# Excelsior488nm_Controller_Schematic.net
KiCad netlist of a schematic drawn in EAGLE
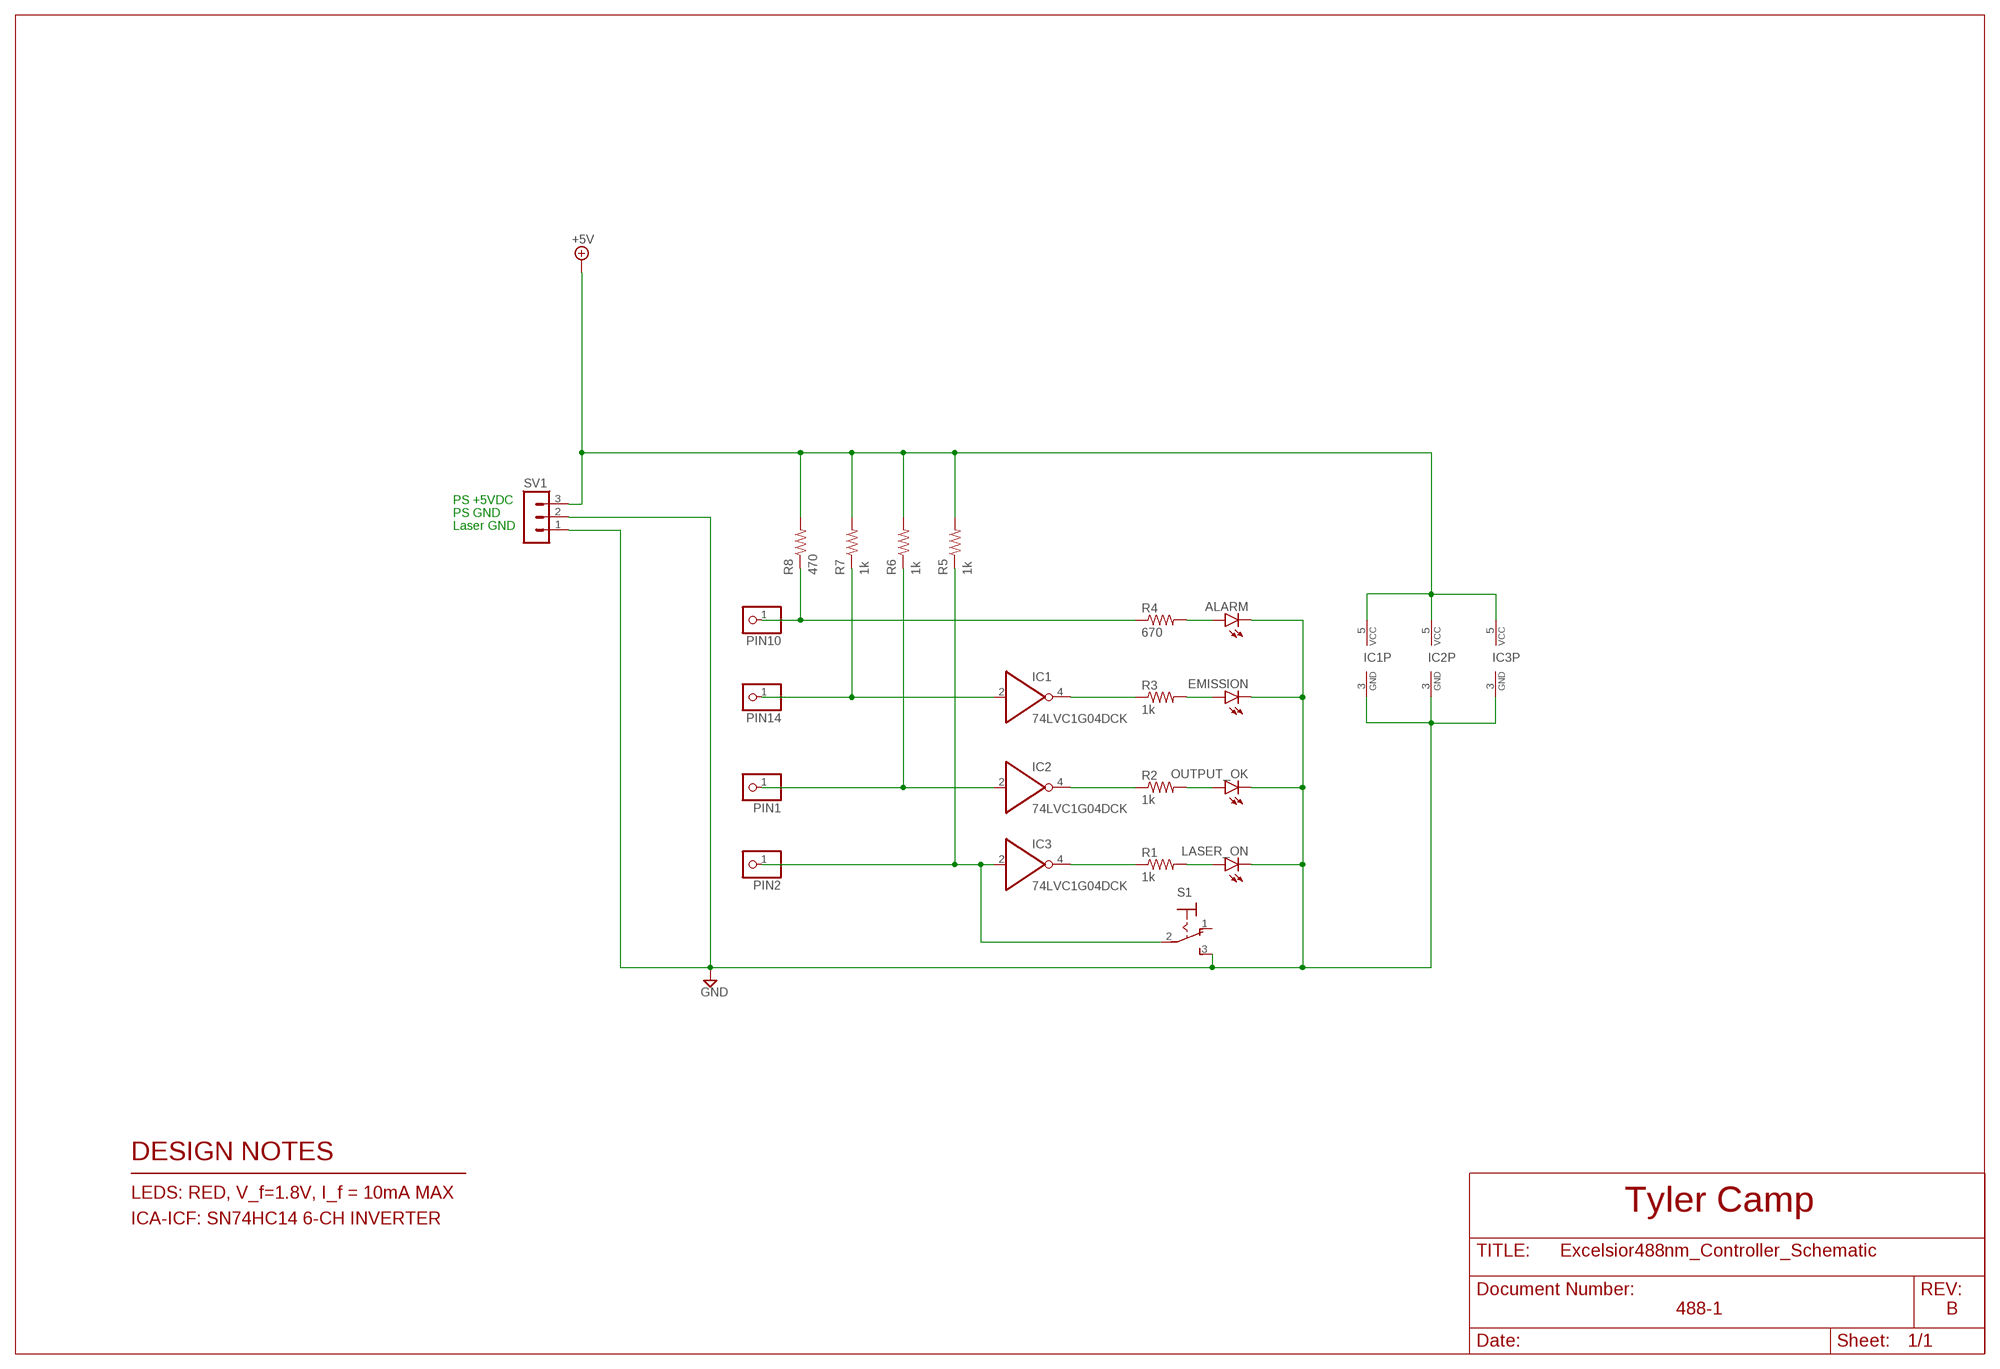
[diagram p0: schematic, sheet 1]

(export (version "E")
  (design (tool "Eeschema 10.0.6"))
  (components
    (comp (ref "ALARM")
      (value "LED3MM")
      (footprint "eagle-import:LED3MM")
      (libsource (lib "eagle-import") (part "LED3MM"))
    )
    (comp (ref "EMISSION")
      (value "LED3MM")
      (footprint "eagle-import:LED3MM")
      (libsource (lib "eagle-import") (part "LED3MM"))
    )
    (comp (ref "IC1")
      (value "74LVC1G04DCK")
      (footprint "eagle-import:SC70-5")
      (libsource (lib "eagle-import") (part "741G04DCKLVC"))
    )
    (comp (ref "IC2")
      (value "74LVC1G04DCK")
      (footprint "eagle-import:SC70-5")
      (libsource (lib "eagle-import") (part "741G04DCKLVC"))
    )
    (comp (ref "IC3")
      (value "74LVC1G04DCK")
      (footprint "eagle-import:SC70-5")
      (libsource (lib "eagle-import") (part "741G04DCKLVC"))
    )
    (comp (ref "LASER_ON")
      (value "LED3MM")
      (footprint "eagle-import:LED3MM")
      (libsource (lib "eagle-import") (part "LED3MM"))
    )
    (comp (ref "OUTPUT_OK")
      (value "LED3MM")
      (footprint "eagle-import:LED3MM")
      (libsource (lib "eagle-import") (part "LED3MM"))
    )
    (comp (ref "PIN1")
      (value "PINHD-1X1")
      (footprint "eagle-import:1X01")
      (libsource (lib "eagle-import") (part "PINHD-1X1"))
    )
    (comp (ref "PIN2")
      (value "PINHD-1X1")
      (footprint "eagle-import:1X01")
      (libsource (lib "eagle-import") (part "PINHD-1X1"))
    )
    (comp (ref "PIN10")
      (value "PINHD-1X1")
      (footprint "eagle-import:1X01")
      (libsource (lib "eagle-import") (part "PINHD-1X1"))
    )
    (comp (ref "PIN14")
      (value "PINHD-1X1")
      (footprint "eagle-import:1X01")
      (libsource (lib "eagle-import") (part "PINHD-1X1"))
    )
    (comp (ref "R1")
      (value "1k")
      (footprint "eagle-import:R0603")
      (libsource (lib "eagle-import") (part "R-US_R0603"))
    )
    (comp (ref "R2")
      (value "1k")
      (footprint "eagle-import:R0603")
      (libsource (lib "eagle-import") (part "R-US_R0603"))
    )
    (comp (ref "R3")
      (value "1k")
      (footprint "eagle-import:R0603")
      (libsource (lib "eagle-import") (part "R-US_R0603"))
    )
    (comp (ref "R4")
      (value "670")
      (footprint "eagle-import:R0603")
      (libsource (lib "eagle-import") (part "R-US_R0603"))
    )
    (comp (ref "R5")
      (value "1k")
      (footprint "eagle-import:R0603")
      (libsource (lib "eagle-import") (part "R-US_R0603"))
    )
    (comp (ref "R6")
      (value "1k")
      (footprint "eagle-import:R0603")
      (libsource (lib "eagle-import") (part "R-US_R0603"))
    )
    (comp (ref "R7")
      (value "1k")
      (footprint "eagle-import:R0603")
      (libsource (lib "eagle-import") (part "R-US_R0603"))
    )
    (comp (ref "R8")
      (value "470")
      (footprint "eagle-import:R0603")
      (libsource (lib "eagle-import") (part "R-US_R0603"))
    )
    (comp (ref "S1")
      (value "M9040P")
      (footprint "eagle-import:M9040P")
      (libsource (lib "eagle-import") (part "M9040P"))
    )
    (comp (ref "SV1")
      (value "MA03-1")
      (footprint "eagle-import:MA03-1")
      (libsource (lib "eagle-import") (part "MA03-1"))
    )
  )
  (nets
    (net (code "1") (name "+5V") (class "Default")
      (node (ref "IC1") (pin "5") (pinfunction "VCC_5") (pintype "power_in"))
      (node (ref "IC2") (pin "5") (pinfunction "VCC_5") (pintype "power_in"))
      (node (ref "IC3") (pin "5") (pinfunction "VCC_5") (pintype "power_in"))
      (node (ref "R5") (pin "2") (pinfunction "2_2") (pintype "passive"))
      (node (ref "R6") (pin "2") (pinfunction "2_2") (pintype "passive"))
      (node (ref "R7") (pin "2") (pinfunction "2_2") (pintype "passive"))
      (node (ref "R8") (pin "2") (pinfunction "2_2") (pintype "passive"))
      (node (ref "SV1") (pin "3") (pinfunction "3_3") (pintype "passive"))
    )
    (net (code "2") (name "GND") (class "Default")
      (node (ref "ALARM") (pin "K") (pinfunction "C_K") (pintype "passive"))
      (node (ref "EMISSION") (pin "K") (pinfunction "C_K") (pintype "passive"))
      (node (ref "IC1") (pin "3") (pinfunction "GND_3") (pintype "power_in"))
      (node (ref "IC2") (pin "3") (pinfunction "GND_3") (pintype "power_in"))
      (node (ref "IC3") (pin "3") (pinfunction "GND_3") (pintype "power_in"))
      (node (ref "LASER_ON") (pin "K") (pinfunction "C_K") (pintype "passive"))
      (node (ref "OUTPUT_OK") (pin "K") (pinfunction "C_K") (pintype "passive"))
      (node (ref "S1") (pin "3") (pinfunction "S_3") (pintype "passive"))
      (node (ref "SV1") (pin "1") (pinfunction "1_1") (pintype "passive"))
      (node (ref "SV1") (pin "2") (pinfunction "2_2") (pintype "passive"))
    )
    (net (code "3") (name "Net-(ALARM-PadA)") (class "Default")
      (node (ref "ALARM") (pin "A") (pinfunction "A_A") (pintype "passive"))
      (node (ref "R4") (pin "2") (pinfunction "2_2") (pintype "passive"))
    )
    (net (code "4") (name "Net-(EMISSION-PadA)") (class "Default")
      (node (ref "EMISSION") (pin "A") (pinfunction "A_A") (pintype "passive"))
      (node (ref "R3") (pin "2") (pinfunction "2_2") (pintype "passive"))
    )
    (net (code "5") (name "Net-(IC1A-I)") (class "Default")
      (node (ref "IC1") (pin "2") (pinfunction "I_2") (pintype "input"))
      (node (ref "PIN14") (pin "1") (pinfunction "1_1") (pintype "passive"))
      (node (ref "R7") (pin "1") (pinfunction "1_1") (pintype "passive"))
    )
    (net (code "6") (name "Net-(IC1A-O)") (class "Default")
      (node (ref "IC1") (pin "4") (pinfunction "O_4") (pintype "output"))
      (node (ref "R3") (pin "1") (pinfunction "1_1") (pintype "passive"))
    )
    (net (code "7") (name "Net-(IC2A-I)") (class "Default")
      (node (ref "IC2") (pin "2") (pinfunction "I_2") (pintype "input"))
      (node (ref "PIN1") (pin "1") (pinfunction "1_1") (pintype "passive"))
      (node (ref "R6") (pin "1") (pinfunction "1_1") (pintype "passive"))
    )
    (net (code "8") (name "Net-(IC2A-O)") (class "Default")
      (node (ref "IC2") (pin "4") (pinfunction "O_4") (pintype "output"))
      (node (ref "R2") (pin "1") (pinfunction "1_1") (pintype "passive"))
    )
    (net (code "9") (name "Net-(IC3A-I)") (class "Default")
      (node (ref "IC3") (pin "2") (pinfunction "I_2") (pintype "input"))
      (node (ref "PIN2") (pin "1") (pinfunction "1_1") (pintype "passive"))
      (node (ref "R5") (pin "1") (pinfunction "1_1") (pintype "passive"))
      (node (ref "S1") (pin "2") (pinfunction "P_2") (pintype "passive"))
    )
    (net (code "10") (name "Net-(IC3A-O)") (class "Default")
      (node (ref "IC3") (pin "4") (pinfunction "O_4") (pintype "output"))
      (node (ref "R1") (pin "1") (pinfunction "1_1") (pintype "passive"))
    )
    (net (code "11") (name "Net-(LASER_ON-PadA)") (class "Default")
      (node (ref "LASER_ON") (pin "A") (pinfunction "A_A") (pintype "passive"))
      (node (ref "R1") (pin "2") (pinfunction "2_2") (pintype "passive"))
    )
    (net (code "12") (name "Net-(OUTPUT_OK-PadA)") (class "Default")
      (node (ref "OUTPUT_OK") (pin "A") (pinfunction "A_A") (pintype "passive"))
      (node (ref "R2") (pin "2") (pinfunction "2_2") (pintype "passive"))
    )
    (net (code "13") (name "Net-(PIN10-Pad1)") (class "Default")
      (node (ref "PIN10") (pin "1") (pinfunction "1_1") (pintype "passive"))
      (node (ref "R4") (pin "1") (pinfunction "1_1") (pintype "passive"))
      (node (ref "R8") (pin "1") (pinfunction "1_1") (pintype "passive"))
    )
    (net (code "14") (name "unconnected-(S1-O-Pad1)") (class "Default")
      (node (ref "S1") (pin "1") (pinfunction "O_1") (pintype "passive"))
    )
  )
)
